# 07-VIDEO_PORT.net
KiCad netlist of a schematic drawn in Altium Designer
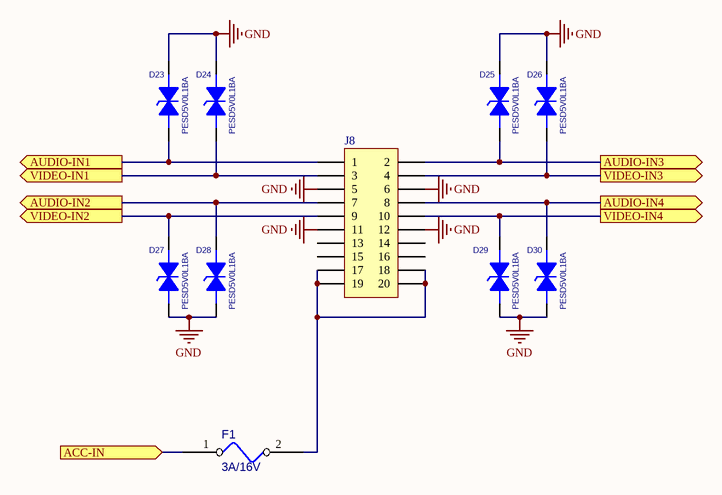
[diagram p0: 07-VIDEO_PORT.SchDoc]

(export (version "E")
  (design (tool "Eeschema 10.0.6"))
  (components
    (comp (ref "D23") (value "PESD5V0L1BA") (libsource (lib "*") (part "PESD")))
    (comp (ref "D24") (value "PESD5V0L1BA") (libsource (lib "*") (part "PESD")))
    (comp (ref "D25") (value "PESD5V0L1BA") (libsource (lib "*") (part "PESD")))
    (comp (ref "D26") (value "PESD5V0L1BA") (libsource (lib "*") (part "PESD")))
    (comp (ref "D27") (value "PESD5V0L1BA") (libsource (lib "*") (part "PESD")))
    (comp (ref "D28") (value "PESD5V0L1BA") (libsource (lib "*") (part "PESD")))
    (comp (ref "D29") (value "PESD5V0L1BA") (libsource (lib "*") (part "PESD")))
    (comp (ref "D30") (value "PESD5V0L1BA") (libsource (lib "*") (part "PESD")))
    (comp (ref "F1") (value "3A/16V") (libsource (lib "*") (part "2A_32VDC_0467-002")))
    (comp (ref "J8")
      (value "Header 10X2")
      (footprint "CONN2X10")
      (description "Header, 10-Pin, Dual row")
      (fields (field (name "PUBLISHER") "Altium Limited"))
      (libsource (lib "Miscellaneous Connectors") (part "Header 10X2"))
    )
  )
  (nets
    (net (code "1") (name "/ACC-IN") (class "Default")
      (node (ref "F1") (pin "1") (pinfunction "1_1") (pintype "passive"))
    )
    (net (code "2") (name "/AUDIO-IN1") (class "Default")
      (node (ref "D23") (pin "1") (pinfunction "1_1") (pintype "passive"))
      (node (ref "J8") (pin "1") (pinfunction "1_1") (pintype "passive"))
    )
    (net (code "3") (name "/AUDIO-IN2") (class "Default")
      (node (ref "D28") (pin "2") (pinfunction "2_2") (pintype "passive"))
      (node (ref "J8") (pin "7") (pinfunction "7_7") (pintype "passive"))
    )
    (net (code "4") (name "/AUDIO-IN3") (class "Default")
      (node (ref "D25") (pin "1") (pinfunction "1_1") (pintype "passive"))
      (node (ref "J8") (pin "2") (pinfunction "2_2") (pintype "passive"))
    )
    (net (code "5") (name "/AUDIO-IN4") (class "Default")
      (node (ref "D30") (pin "2") (pinfunction "2_2") (pintype "passive"))
      (node (ref "J8") (pin "8") (pinfunction "8_8") (pintype "passive"))
    )
    (net (code "6") (name "/VIDEO-IN1") (class "Default")
      (node (ref "D24") (pin "1") (pinfunction "1_1") (pintype "passive"))
      (node (ref "J8") (pin "3") (pinfunction "3_3") (pintype "passive"))
    )
    (net (code "7") (name "/VIDEO-IN2") (class "Default")
      (node (ref "D27") (pin "2") (pinfunction "2_2") (pintype "passive"))
      (node (ref "J8") (pin "9") (pinfunction "9_9") (pintype "passive"))
    )
    (net (code "8") (name "/VIDEO-IN3") (class "Default")
      (node (ref "D26") (pin "1") (pinfunction "1_1") (pintype "passive"))
      (node (ref "J8") (pin "4") (pinfunction "4_4") (pintype "passive"))
    )
    (net (code "9") (name "/VIDEO-IN4") (class "Default")
      (node (ref "D29") (pin "2") (pinfunction "2_2") (pintype "passive"))
      (node (ref "J8") (pin "10") (pinfunction "10_10") (pintype "passive"))
    )
    (net (code "10") (name "GND") (class "Default")
      (node (ref "D23") (pin "2") (pinfunction "2_2") (pintype "passive"))
      (node (ref "D24") (pin "2") (pinfunction "2_2") (pintype "passive"))
      (node (ref "D25") (pin "2") (pinfunction "2_2") (pintype "passive"))
      (node (ref "D26") (pin "2") (pinfunction "2_2") (pintype "passive"))
      (node (ref "D27") (pin "1") (pinfunction "1_1") (pintype "passive"))
      (node (ref "D28") (pin "1") (pinfunction "1_1") (pintype "passive"))
      (node (ref "D29") (pin "1") (pinfunction "1_1") (pintype "passive"))
      (node (ref "D30") (pin "1") (pinfunction "1_1") (pintype "passive"))
      (node (ref "J8") (pin "11") (pinfunction "11_11") (pintype "passive"))
      (node (ref "J8") (pin "12") (pinfunction "12_12") (pintype "passive"))
      (node (ref "J8") (pin "5") (pinfunction "5_5") (pintype "passive"))
      (node (ref "J8") (pin "6") (pinfunction "6_6") (pintype "passive"))
    )
    (net (code "11") (name "Net-(F1-Pad2)") (class "Default")
      (node (ref "F1") (pin "2") (pinfunction "2_2") (pintype "passive"))
      (node (ref "J8") (pin "17") (pinfunction "17_17") (pintype "passive"))
      (node (ref "J8") (pin "18") (pinfunction "18_18") (pintype "passive"))
      (node (ref "J8") (pin "19") (pinfunction "19_19") (pintype "passive"))
      (node (ref "J8") (pin "20") (pinfunction "20_20") (pintype "passive"))
    )
    (net (code "12") (name "unconnected-(J8-Pad13)") (class "Default")
      (node (ref "J8") (pin "13") (pinfunction "13_13") (pintype "passive"))
    )
    (net (code "13") (name "unconnected-(J8-Pad14)") (class "Default")
      (node (ref "J8") (pin "14") (pinfunction "14_14") (pintype "passive"))
    )
    (net (code "14") (name "unconnected-(J8-Pad15)") (class "Default")
      (node (ref "J8") (pin "15") (pinfunction "15_15") (pintype "passive"))
    )
    (net (code "15") (name "unconnected-(J8-Pad16)") (class "Default")
      (node (ref "J8") (pin "16") (pinfunction "16_16") (pintype "passive"))
    )
  )
)
